# Pin_Function_Relays.net
KiCad netlist of a schematic drawn in Altium Designer
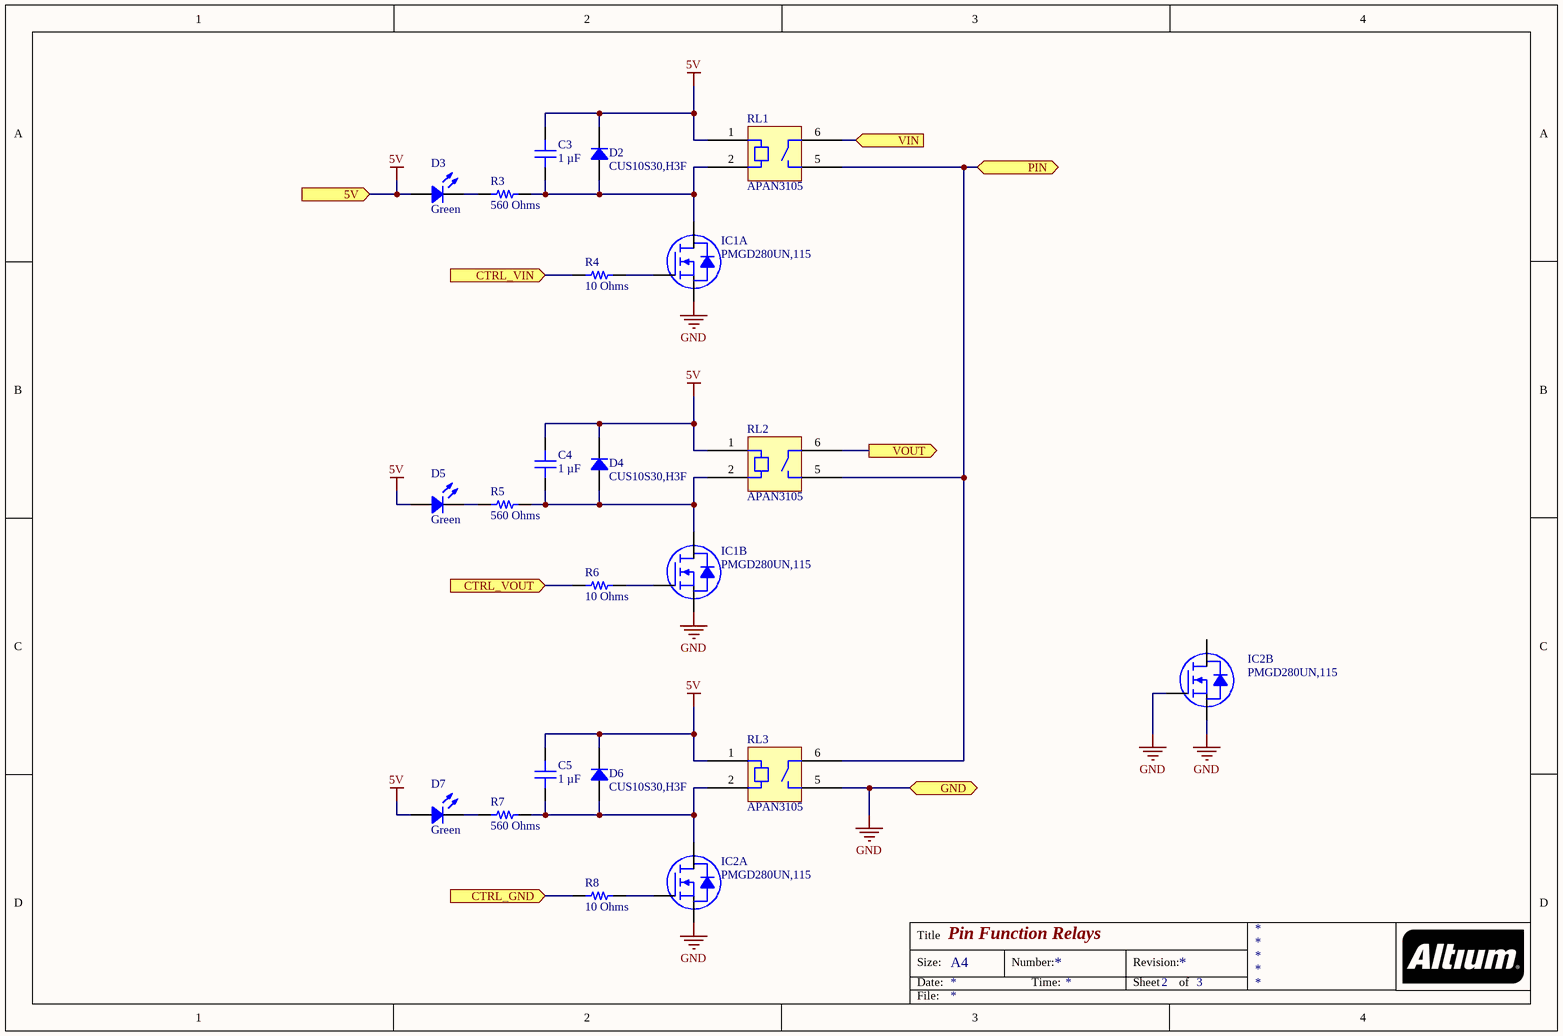
[diagram p0: Pin Function Relays.SchDoc]

(export (version "E")
  (design (tool "Eeschema 10.0.6"))
  (components
    (comp (ref "C3")
      (value "1 µF")
      (footprint "CAP 0603_1608")
      (description "CAP CER 1UF 25V X7R 0603")
      (fields
        (field (name "PART NUMBER") "GCM188R71E105KA64D")
        (field (name "MANUFACTURER") "Murata Electronics")
      )
      (libsource (lib "altiumlibrary.com") (part "Capacitor"))
    )
    (comp (ref "C4")
      (value "1 µF")
      (footprint "CAP 0603_1608")
      (description "CAP CER 1UF 25V X7R 0603")
      (fields
        (field (name "PART NUMBER") "GCM188R71E105KA64D")
        (field (name "MANUFACTURER") "Murata Electronics")
      )
      (libsource (lib "altiumlibrary.com") (part "Capacitor"))
    )
    (comp (ref "C5")
      (value "1 µF")
      (footprint "CAP 0603_1608")
      (description "CAP CER 1UF 25V X7R 0603")
      (fields
        (field (name "PART NUMBER") "GCM188R71E105KA64D")
        (field (name "MANUFACTURER") "Murata Electronics")
      )
      (libsource (lib "altiumlibrary.com") (part "Capacitor"))
    )
    (comp (ref "D2")
      (value "CUS10S30,H3F")
      (footprint "SOD323")
      (description "DIODE SCHOTTKY 30V 1A USC")
      (fields (field (name "MANUFACTURER") "Toshiba Semiconductor and Storage"))
      (libsource (lib "altiumlibrary.com") (part "Diode"))
    )
    (comp (ref "D3")
      (value "Green")
      (footprint "LED 0603_1608 GREEN")
      (description "LED GREEN DIFFUSED SMD")
      (fields
        (field (name "PART NUMBER") "SML-LX0603GW-TR")
        (field (name "MANUFACTURER") "Lumex Opto/Components Inc.")
      )
      (libsource (lib "altiumlibrary.com") (part "LED"))
    )
    (comp (ref "D4")
      (value "CUS10S30,H3F")
      (footprint "SOD323")
      (description "DIODE SCHOTTKY 30V 1A USC")
      (fields (field (name "MANUFACTURER") "Toshiba Semiconductor and Storage"))
      (libsource (lib "altiumlibrary.com") (part "Diode"))
    )
    (comp (ref "D5")
      (value "Green")
      (footprint "LED 0603_1608 GREEN")
      (description "LED GREEN DIFFUSED SMD")
      (fields
        (field (name "PART NUMBER") "SML-LX0603GW-TR")
        (field (name "MANUFACTURER") "Lumex Opto/Components Inc.")
      )
      (libsource (lib "altiumlibrary.com") (part "LED"))
    )
    (comp (ref "D6")
      (value "CUS10S30,H3F")
      (footprint "SOD323")
      (description "DIODE SCHOTTKY 30V 1A USC")
      (fields (field (name "MANUFACTURER") "Toshiba Semiconductor and Storage"))
      (libsource (lib "altiumlibrary.com") (part "Diode"))
    )
    (comp (ref "D7")
      (value "Green")
      (footprint "LED 0603_1608 GREEN")
      (description "LED GREEN DIFFUSED SMD")
      (fields
        (field (name "PART NUMBER") "SML-LX0603GW-TR")
        (field (name "MANUFACTURER") "Lumex Opto/Components Inc.")
      )
      (libsource (lib "altiumlibrary.com") (part "LED"))
    )
    (comp (ref "IC1")
      (value "PMGD280UN,115")
      (footprint "NXP SOT-363")
      (description "MOSFET 2N-CH 20V 0.87A 6TSSOP")
      (fields (field (name "MANUFACTURER") "Nexperia USA Inc."))
      (libsource (lib "altiumlibrary.com") (part "NEXPERIA DUAL MOSFET N-CH SOT363"))
    )
    (comp (ref "IC2")
      (value "PMGD280UN,115")
      (footprint "NXP SOT-363")
      (description "MOSFET 2N-CH 20V 0.87A 6TSSOP")
      (fields (field (name "MANUFACTURER") "Nexperia USA Inc."))
      (libsource (lib "altiumlibrary.com") (part "NEXPERIA DUAL MOSFET N-CH SOT363"))
    )
    (comp (ref "R3")
      (value "560 Ohms")
      (footprint "RES 0603_1608")
      (description "RES 560 OHM 1% 1/10W 0603")
      (fields (field (name "PART NUMBER") "RC0603FR-07560RL") (field (name "MANUFACTURER") "Yageo"))
      (libsource (lib "altiumlibrary.com") (part "Resistor"))
    )
    (comp (ref "R4")
      (value "10 Ohms")
      (footprint "RES 0603_1608")
      (description "RES 10 OHM 1% 1/10W 0603")
      (fields (field (name "PART NUMBER") "RC0603FR-0710RL") (field (name "MANUFACTURER") "Yageo"))
      (libsource (lib "altiumlibrary.com") (part "Resistor"))
    )
    (comp (ref "R5")
      (value "560 Ohms")
      (footprint "RES 0603_1608")
      (description "RES 560 OHM 1% 1/10W 0603")
      (fields (field (name "PART NUMBER") "RC0603FR-07560RL") (field (name "MANUFACTURER") "Yageo"))
      (libsource (lib "altiumlibrary.com") (part "Resistor"))
    )
    (comp (ref "R6")
      (value "10 Ohms")
      (footprint "RES 0603_1608")
      (description "RES 10 OHM 1% 1/10W 0603")
      (fields (field (name "PART NUMBER") "RC0603FR-0710RL") (field (name "MANUFACTURER") "Yageo"))
      (libsource (lib "altiumlibrary.com") (part "Resistor"))
    )
    (comp (ref "R7")
      (value "560 Ohms")
      (footprint "RES 0603_1608")
      (description "RES 560 OHM 1% 1/10W 0603")
      (fields (field (name "PART NUMBER") "RC0603FR-07560RL") (field (name "MANUFACTURER") "Yageo"))
      (libsource (lib "altiumlibrary.com") (part "Resistor"))
    )
    (comp (ref "R8")
      (value "10 Ohms")
      (footprint "RES 0603_1608")
      (description "RES 10 OHM 1% 1/10W 0603")
      (fields (field (name "PART NUMBER") "RC0603FR-0710RL") (field (name "MANUFACTURER") "Yageo"))
      (libsource (lib "altiumlibrary.com") (part "Resistor"))
    )
    (comp (ref "RL1")
      (value "APAN3105")
      (footprint "PANASONIC APAN31nn PA-N")
      (description "RELAY GENERAL PURPOSE SPST 5A 5V")
      (fields (field (name "MANUFACTURER") "Panasonic Electric Works"))
      (libsource (lib "altiumlibrary.com") (part "PANASONIC APAN31NN PA-N"))
    )
    (comp (ref "RL2")
      (value "APAN3105")
      (footprint "PANASONIC APAN31nn PA-N")
      (description "RELAY GENERAL PURPOSE SPST 5A 5V")
      (fields (field (name "MANUFACTURER") "Panasonic Electric Works"))
      (libsource (lib "altiumlibrary.com") (part "PANASONIC APAN31NN PA-N"))
    )
    (comp (ref "RL3")
      (value "APAN3105")
      (footprint "PANASONIC APAN31nn PA-N")
      (description "RELAY GENERAL PURPOSE SPST 5A 5V")
      (fields (field (name "MANUFACTURER") "Panasonic Electric Works"))
      (libsource (lib "altiumlibrary.com") (part "PANASONIC APAN31NN PA-N"))
    )
  )
  (nets
    (net (code "1") (name "/CTRL_GND") (class "Default")
      (node (ref "R8") (pin "1") (pinfunction "1_1") (pintype "passive"))
    )
    (net (code "2") (name "/CTRL_VIN") (class "Default")
      (node (ref "R4") (pin "1") (pinfunction "1_1") (pintype "passive"))
    )
    (net (code "3") (name "/CTRL_VOUT") (class "Default")
      (node (ref "R6") (pin "1") (pinfunction "1_1") (pintype "passive"))
    )
    (net (code "4") (name "/PIN") (class "Default")
      (node (ref "RL1") (pin "5") (pinfunction "TERM1_5") (pintype "passive"))
      (node (ref "RL2") (pin "5") (pinfunction "TERM1_5") (pintype "passive"))
      (node (ref "RL3") (pin "6") (pinfunction "TERM2_6") (pintype "passive"))
    )
    (net (code "5") (name "/VIN") (class "Default")
      (node (ref "RL1") (pin "6") (pinfunction "TERM2_6") (pintype "passive"))
    )
    (net (code "6") (name "/VOUT") (class "Default")
      (node (ref "RL2") (pin "6") (pinfunction "TERM2_6") (pintype "passive"))
    )
    (net (code "7") (name "5V") (class "Default")
      (node (ref "C3") (pin "2") (pinfunction "2_2") (pintype "passive"))
      (node (ref "C4") (pin "2") (pinfunction "2_2") (pintype "passive"))
      (node (ref "C5") (pin "2") (pinfunction "2_2") (pintype "passive"))
      (node (ref "D2") (pin "2") (pinfunction "2_2") (pintype "passive"))
      (node (ref "D3") (pin "1") (pinfunction "1_1") (pintype "passive"))
      (node (ref "D4") (pin "2") (pinfunction "2_2") (pintype "passive"))
      (node (ref "D5") (pin "1") (pinfunction "1_1") (pintype "passive"))
      (node (ref "D6") (pin "2") (pinfunction "2_2") (pintype "passive"))
      (node (ref "D7") (pin "1") (pinfunction "1_1") (pintype "passive"))
      (node (ref "RL1") (pin "1") (pinfunction "COIL1_1") (pintype "passive"))
      (node (ref "RL2") (pin "1") (pinfunction "COIL1_1") (pintype "passive"))
      (node (ref "RL3") (pin "1") (pinfunction "COIL1_1") (pintype "passive"))
    )
    (net (code "8") (name "GND") (class "Default")
      (node (ref "IC1") (pin "1") (pinfunction "S1_1") (pintype "passive"))
      (node (ref "IC1") (pin "4") (pinfunction "S2_4") (pintype "passive"))
      (node (ref "IC2") (pin "1") (pinfunction "S1_1") (pintype "passive"))
      (node (ref "IC2") (pin "4") (pinfunction "S2_4") (pintype "passive"))
      (node (ref "IC2") (pin "5") (pinfunction "G2_5") (pintype "passive"))
      (node (ref "RL3") (pin "5") (pinfunction "TERM1_5") (pintype "passive"))
    )
    (net (code "9") (name "Net-(D3-Pad2)") (class "Default")
      (node (ref "D3") (pin "2") (pinfunction "2_2") (pintype "passive"))
      (node (ref "R3") (pin "1") (pinfunction "1_1") (pintype "passive"))
    )
    (net (code "10") (name "Net-(D5-Pad2)") (class "Default")
      (node (ref "D5") (pin "2") (pinfunction "2_2") (pintype "passive"))
      (node (ref "R5") (pin "1") (pinfunction "1_1") (pintype "passive"))
    )
    (net (code "11") (name "Net-(D7-Pad2)") (class "Default")
      (node (ref "D7") (pin "2") (pinfunction "2_2") (pintype "passive"))
      (node (ref "R7") (pin "1") (pinfunction "1_1") (pintype "passive"))
    )
    (net (code "12") (name "Net-(IC1A-D1)") (class "Default")
      (node (ref "C3") (pin "1") (pinfunction "1_1") (pintype "passive"))
      (node (ref "D2") (pin "1") (pinfunction "1_1") (pintype "passive"))
      (node (ref "IC1") (pin "6") (pinfunction "D1_6") (pintype "passive"))
      (node (ref "R3") (pin "2") (pinfunction "2_2") (pintype "passive"))
      (node (ref "RL1") (pin "2") (pinfunction "COIL2_2") (pintype "passive"))
    )
    (net (code "13") (name "Net-(IC1A-G1)") (class "Default")
      (node (ref "IC1") (pin "2") (pinfunction "G1_2") (pintype "passive"))
      (node (ref "R4") (pin "2") (pinfunction "2_2") (pintype "passive"))
    )
    (net (code "14") (name "Net-(IC1B-D2)") (class "Default")
      (node (ref "C4") (pin "1") (pinfunction "1_1") (pintype "passive"))
      (node (ref "D4") (pin "1") (pinfunction "1_1") (pintype "passive"))
      (node (ref "IC1") (pin "3") (pinfunction "D2_3") (pintype "passive"))
      (node (ref "R5") (pin "2") (pinfunction "2_2") (pintype "passive"))
      (node (ref "RL2") (pin "2") (pinfunction "COIL2_2") (pintype "passive"))
    )
    (net (code "15") (name "Net-(IC1B-G2)") (class "Default")
      (node (ref "IC1") (pin "5") (pinfunction "G2_5") (pintype "passive"))
      (node (ref "R6") (pin "2") (pinfunction "2_2") (pintype "passive"))
    )
    (net (code "16") (name "Net-(IC2A-D1)") (class "Default")
      (node (ref "C5") (pin "1") (pinfunction "1_1") (pintype "passive"))
      (node (ref "D6") (pin "1") (pinfunction "1_1") (pintype "passive"))
      (node (ref "IC2") (pin "6") (pinfunction "D1_6") (pintype "passive"))
      (node (ref "R7") (pin "2") (pinfunction "2_2") (pintype "passive"))
      (node (ref "RL3") (pin "2") (pinfunction "COIL2_2") (pintype "passive"))
    )
    (net (code "17") (name "Net-(IC2A-G1)") (class "Default")
      (node (ref "IC2") (pin "2") (pinfunction "G1_2") (pintype "passive"))
      (node (ref "R8") (pin "2") (pinfunction "2_2") (pintype "passive"))
    )
    (net (code "18") (name "unconnected-(IC2B-D2-Pad3)") (class "Default")
      (node (ref "IC2") (pin "3") (pinfunction "D2_3") (pintype "passive"))
    )
  )
)
